# CRLH-v1_2.net
KiCad netlist of a schematic drawn in EAGLE
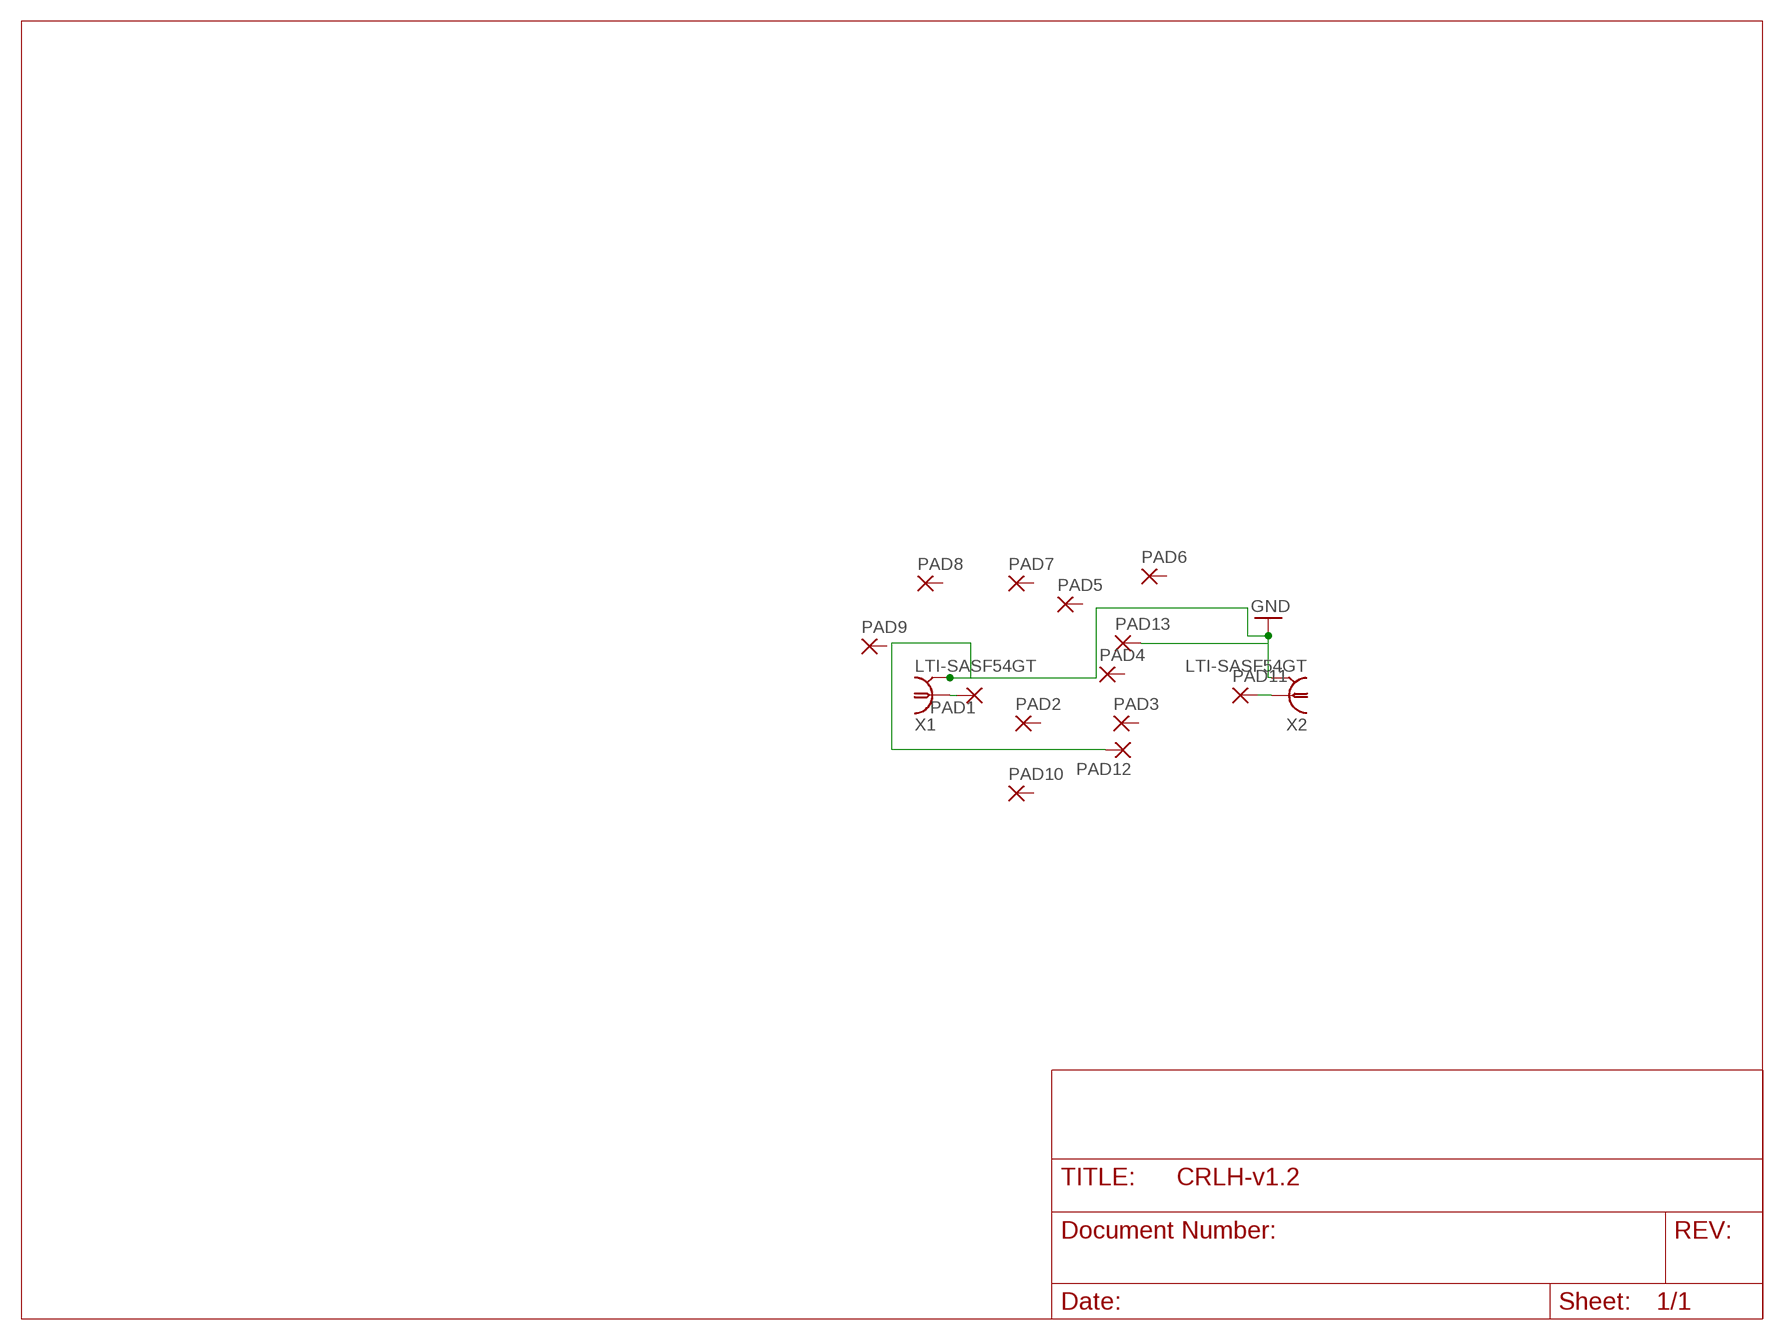
[diagram p0: schematic, sheet 1]

(export (version "E")
  (design (tool "Eeschema 10.0.6"))
  (components
    (comp (ref "PAD1")
      (value "SMD5")
      (footprint "eagle-import:SMD2,54-5,08")
      (libsource (lib "eagle-import") (part "SMD5"))
    )
    (comp (ref "PAD2")
      (value "SMD5")
      (footprint "eagle-import:SMD2,54-5,08")
      (libsource (lib "eagle-import") (part "SMD5"))
    )
    (comp (ref "PAD3")
      (value "SMD5")
      (footprint "eagle-import:SMD2,54-5,08")
      (libsource (lib "eagle-import") (part "SMD5"))
    )
    (comp (ref "PAD4")
      (value "SMD5")
      (footprint "eagle-import:SMD2,54-5,08")
      (libsource (lib "eagle-import") (part "SMD5"))
    )
    (comp (ref "PAD5")
      (value "SMD5")
      (footprint "eagle-import:SMD2,54-5,08")
      (libsource (lib "eagle-import") (part "SMD5"))
    )
    (comp (ref "PAD6")
      (value "SMD5")
      (footprint "eagle-import:SMD2,54-5,08")
      (libsource (lib "eagle-import") (part "SMD5"))
    )
    (comp (ref "PAD7")
      (value "SMD5")
      (footprint "eagle-import:SMD2,54-5,08")
      (libsource (lib "eagle-import") (part "SMD5"))
    )
    (comp (ref "PAD8")
      (value "SMD5")
      (footprint "eagle-import:SMD2,54-5,08")
      (libsource (lib "eagle-import") (part "SMD5"))
    )
    (comp (ref "PAD9")
      (value "SMD5")
      (footprint "eagle-import:SMD2,54-5,08")
      (libsource (lib "eagle-import") (part "SMD5"))
    )
    (comp (ref "PAD10")
      (value "SMD5")
      (footprint "eagle-import:SMD2,54-5,08")
      (libsource (lib "eagle-import") (part "SMD5"))
    )
    (comp (ref "PAD11")
      (value "SMD5")
      (footprint "eagle-import:SMD2,54-5,08")
      (libsource (lib "eagle-import") (part "pad1x3mm_SMD5"))
    )
    (comp (ref "PAD12")
      (value "SMD5")
      (footprint "eagle-import:SMD2,54-5,08")
      (libsource (lib "eagle-import") (part "pad97x2mm_SMD5"))
    )
    (comp (ref "PAD13")
      (value "SMD5")
      (footprint "eagle-import:SMD2,54-5,08")
      (libsource (lib "eagle-import") (part "pad97x2mm_SMD5"))
    )
    (comp (ref "X1")
      (value "LTI-SASF54GT")
      (footprint "eagle-import:LTI-SASF54GT")
      (libsource (lib "eagle-import") (part "LTI-SASF54GT"))
    )
    (comp (ref "X2")
      (value "LTI-SASF54GT")
      (footprint "eagle-import:LTI-SASF54GT")
      (libsource (lib "eagle-import") (part "LTI-SASF54GT"))
    )
  )
  (nets
    (net (code "1") (name "GND") (class "Default")
      (node (ref "PAD12") (pin "1") (pinfunction "P_1") (pintype "passive"))
      (node (ref "PAD13") (pin "1") (pinfunction "P_1") (pintype "passive"))
      (node (ref "X1") (pin "2") (pinfunction "2_2") (pintype "passive"))
      (node (ref "X1") (pin "3") (pinfunction "2_3") (pintype "passive"))
      (node (ref "X1") (pin "4") (pinfunction "2_4") (pintype "passive"))
      (node (ref "X1") (pin "5") (pinfunction "2_5") (pintype "passive"))
      (node (ref "X2") (pin "2") (pinfunction "2_2") (pintype "passive"))
      (node (ref "X2") (pin "3") (pinfunction "2_3") (pintype "passive"))
      (node (ref "X2") (pin "4") (pinfunction "2_4") (pintype "passive"))
      (node (ref "X2") (pin "5") (pinfunction "2_5") (pintype "passive"))
    )
    (net (code "2") (name "Net-(PAD1-P)") (class "Default")
      (node (ref "PAD1") (pin "1") (pinfunction "P_1") (pintype "passive"))
      (node (ref "X1") (pin "1") (pinfunction "1_1") (pintype "passive"))
    )
    (net (code "3") (name "Net-(PAD11-P)") (class "Default")
      (node (ref "PAD11") (pin "1") (pinfunction "P_1") (pintype "passive"))
      (node (ref "X2") (pin "1") (pinfunction "1_1") (pintype "passive"))
    )
    (net (code "4") (name "unconnected-(PAD2-P-Pad1)") (class "Default")
      (node (ref "PAD2") (pin "1") (pinfunction "P_1") (pintype "passive"))
    )
    (net (code "5") (name "unconnected-(PAD3-P-Pad1)") (class "Default")
      (node (ref "PAD3") (pin "1") (pinfunction "P_1") (pintype "passive"))
    )
    (net (code "6") (name "unconnected-(PAD4-P-Pad1)") (class "Default")
      (node (ref "PAD4") (pin "1") (pinfunction "P_1") (pintype "passive"))
    )
    (net (code "7") (name "unconnected-(PAD5-P-Pad1)") (class "Default")
      (node (ref "PAD5") (pin "1") (pinfunction "P_1") (pintype "passive"))
    )
    (net (code "8") (name "unconnected-(PAD6-P-Pad1)") (class "Default")
      (node (ref "PAD6") (pin "1") (pinfunction "P_1") (pintype "passive"))
    )
    (net (code "9") (name "unconnected-(PAD7-P-Pad1)") (class "Default")
      (node (ref "PAD7") (pin "1") (pinfunction "P_1") (pintype "passive"))
    )
    (net (code "10") (name "unconnected-(PAD8-P-Pad1)") (class "Default")
      (node (ref "PAD8") (pin "1") (pinfunction "P_1") (pintype "passive"))
    )
    (net (code "11") (name "unconnected-(PAD9-P-Pad1)") (class "Default")
      (node (ref "PAD9") (pin "1") (pinfunction "P_1") (pintype "passive"))
    )
    (net (code "12") (name "unconnected-(PAD10-P-Pad1)") (class "Default")
      (node (ref "PAD10") (pin "1") (pinfunction "P_1") (pintype "passive"))
    )
  )
)
